# investigator_regulator.net
KiCad netlist of a schematic drawn in Altium Designer
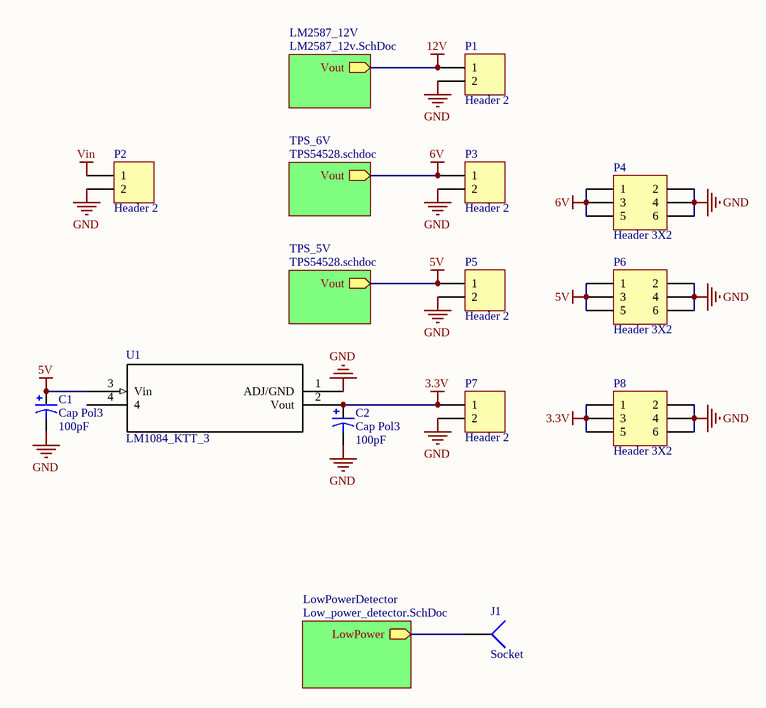
[diagram p0: investigator_regulator.SchDoc]

(export (version "E")
  (design (tool "Eeschema 10.0.6"))
  (components
    (comp (ref "C1")
      (value "Cap Pol3")
      (footprint "AXIAL-0.3")
      (description "Polarized Capacitor (Surface Mount)")
      (fields (field (name "ALTIUM_VALUE") "100pF") (field (name "PUBLISHER") "Altium Limited"))
      (libsource (lib "Miscellaneous Devices") (part "Cap Pol3"))
    )
    (comp (ref "C2")
      (value "Cap Pol3")
      (footprint "AXIAL-0.3")
      (description "Polarized Capacitor (Surface Mount)")
      (fields (field (name "ALTIUM_VALUE") "100pF") (field (name "PUBLISHER") "Altium Limited"))
      (libsource (lib "Miscellaneous Devices") (part "Cap Pol3"))
    )
    (comp (ref "J1")
      (value "Socket")
      (footprint "PIN1")
      (fields (field (name "PUBLISHER") "Altium Limited"))
      (libsource (lib "Miscellaneous Connectors") (part "Socket"))
    )
    (comp (ref "P1")
      (value "Header 2")
      (footprint "WireHeader")
      (description "Header, 2-Pin")
      (fields (field (name "PUBLISHER") "Altium Limited"))
      (libsource (lib "Miscellaneous Connectors") (part "Header 2"))
    )
    (comp (ref "P2")
      (value "Header 2")
      (footprint "WireHeader")
      (description "Header, 2-Pin")
      (fields (field (name "PUBLISHER") "Altium Limited"))
      (libsource (lib "Miscellaneous Connectors") (part "Header 2"))
    )
    (comp (ref "P3")
      (value "Header 2")
      (footprint "WireHeader")
      (description "Header, 2-Pin")
      (fields (field (name "PUBLISHER") "Altium Limited"))
      (libsource (lib "Miscellaneous Connectors") (part "Header 2"))
    )
    (comp (ref "P4")
      (value "Header 3X2")
      (footprint "HDR2X3")
      (description "Header, 3-Pin, Dual row")
      (fields (field (name "PUBLISHER") "Altium Limited"))
      (libsource (lib "Miscellaneous Connectors") (part "Header 3X2"))
    )
    (comp (ref "P5")
      (value "Header 2")
      (footprint "WireHeader")
      (description "Header, 2-Pin")
      (fields (field (name "PUBLISHER") "Altium Limited"))
      (libsource (lib "Miscellaneous Connectors") (part "Header 2"))
    )
    (comp (ref "P6")
      (value "Header 3X2")
      (footprint "HDR2X3")
      (description "Header, 3-Pin, Dual row")
      (fields (field (name "PUBLISHER") "Altium Limited"))
      (libsource (lib "Miscellaneous Connectors") (part "Header 3X2"))
    )
    (comp (ref "P7")
      (value "Header 2")
      (footprint "WireHeader")
      (description "Header, 2-Pin")
      (fields (field (name "PUBLISHER") "Altium Limited"))
      (libsource (lib "Miscellaneous Connectors") (part "Header 2"))
    )
    (comp (ref "P8")
      (value "Header 3X2")
      (footprint "HDR2X3")
      (description "Header, 3-Pin, Dual row")
      (fields (field (name "PUBLISHER") "Altium Limited"))
      (libsource (lib "Miscellaneous Connectors") (part "Header 3X2"))
    )
    (comp (ref "U1")
      (value "LM1084_KTT_3")
      (footprint "TS3B")
      (description "Imported")
      (fields (field (name "PARTNUMBER") "LM1084IS-33"))
      (libsource (lib "LM1084") (part "LM1084_KTT_3"))
    )
  )
  (nets
    (net (code "1") (name "/LowPower") (class "Default")
      (node (ref "J1") (pin "1") (pinfunction "1_1") (pintype "passive"))
    )
    (net (code "2") (name "3.3V") (class "Default")
      (node (ref "C2") (pin "1") (pinfunction "1_1") (pintype "passive"))
      (node (ref "P7") (pin "1") (pinfunction "1_1") (pintype "passive"))
      (node (ref "P8") (pin "1") (pinfunction "1_1") (pintype "passive"))
      (node (ref "P8") (pin "3") (pinfunction "3_3") (pintype "passive"))
      (node (ref "P8") (pin "5") (pinfunction "5_5") (pintype "passive"))
      (node (ref "U1") (pin "2") (pinfunction "Vout_2") (pintype "passive"))
    )
    (net (code "3") (name "5V") (class "Default")
      (node (ref "C1") (pin "1") (pinfunction "1_1") (pintype "passive"))
      (node (ref "P5") (pin "1") (pinfunction "1_1") (pintype "passive"))
      (node (ref "P6") (pin "1") (pinfunction "1_1") (pintype "passive"))
      (node (ref "P6") (pin "3") (pinfunction "3_3") (pintype "passive"))
      (node (ref "P6") (pin "5") (pinfunction "5_5") (pintype "passive"))
      (node (ref "U1") (pin "3") (pinfunction "Vin_3") (pintype "input"))
    )
    (net (code "4") (name "6V") (class "Default")
      (node (ref "P3") (pin "1") (pinfunction "1_1") (pintype "passive"))
      (node (ref "P4") (pin "1") (pinfunction "1_1") (pintype "passive"))
      (node (ref "P4") (pin "3") (pinfunction "3_3") (pintype "passive"))
      (node (ref "P4") (pin "5") (pinfunction "5_5") (pintype "passive"))
    )
    (net (code "5") (name "12V") (class "Default")
      (node (ref "P1") (pin "1") (pinfunction "1_1") (pintype "passive"))
    )
    (net (code "6") (name "GND") (class "Default")
      (node (ref "C1") (pin "2") (pinfunction "2_2") (pintype "passive"))
      (node (ref "C2") (pin "2") (pinfunction "2_2") (pintype "passive"))
      (node (ref "P1") (pin "2") (pinfunction "2_2") (pintype "passive"))
      (node (ref "P2") (pin "2") (pinfunction "2_2") (pintype "passive"))
      (node (ref "P3") (pin "2") (pinfunction "2_2") (pintype "passive"))
      (node (ref "P4") (pin "2") (pinfunction "2_2") (pintype "passive"))
      (node (ref "P4") (pin "4") (pinfunction "4_4") (pintype "passive"))
      (node (ref "P4") (pin "6") (pinfunction "6_6") (pintype "passive"))
      (node (ref "P5") (pin "2") (pinfunction "2_2") (pintype "passive"))
      (node (ref "P6") (pin "2") (pinfunction "2_2") (pintype "passive"))
      (node (ref "P6") (pin "4") (pinfunction "4_4") (pintype "passive"))
      (node (ref "P6") (pin "6") (pinfunction "6_6") (pintype "passive"))
      (node (ref "P7") (pin "2") (pinfunction "2_2") (pintype "passive"))
      (node (ref "P8") (pin "2") (pinfunction "2_2") (pintype "passive"))
      (node (ref "P8") (pin "4") (pinfunction "4_4") (pintype "passive"))
      (node (ref "P8") (pin "6") (pinfunction "6_6") (pintype "passive"))
      (node (ref "U1") (pin "1") (pinfunction "ADJ/GND_1") (pintype "passive"))
    )
    (net (code "7") (name "Vin") (class "Default")
      (node (ref "P2") (pin "1") (pinfunction "1_1") (pintype "passive"))
    )
    (net (code "8") (name "unconnected-(U1-Pad4)") (class "Default")
      (node (ref "U1") (pin "4") (pinfunction "4_4") (pintype "passive"))
    )
  )
)
